# TCAN1146_PWR_MGMT.net
KiCad netlist of a schematic drawn in Altium Designer
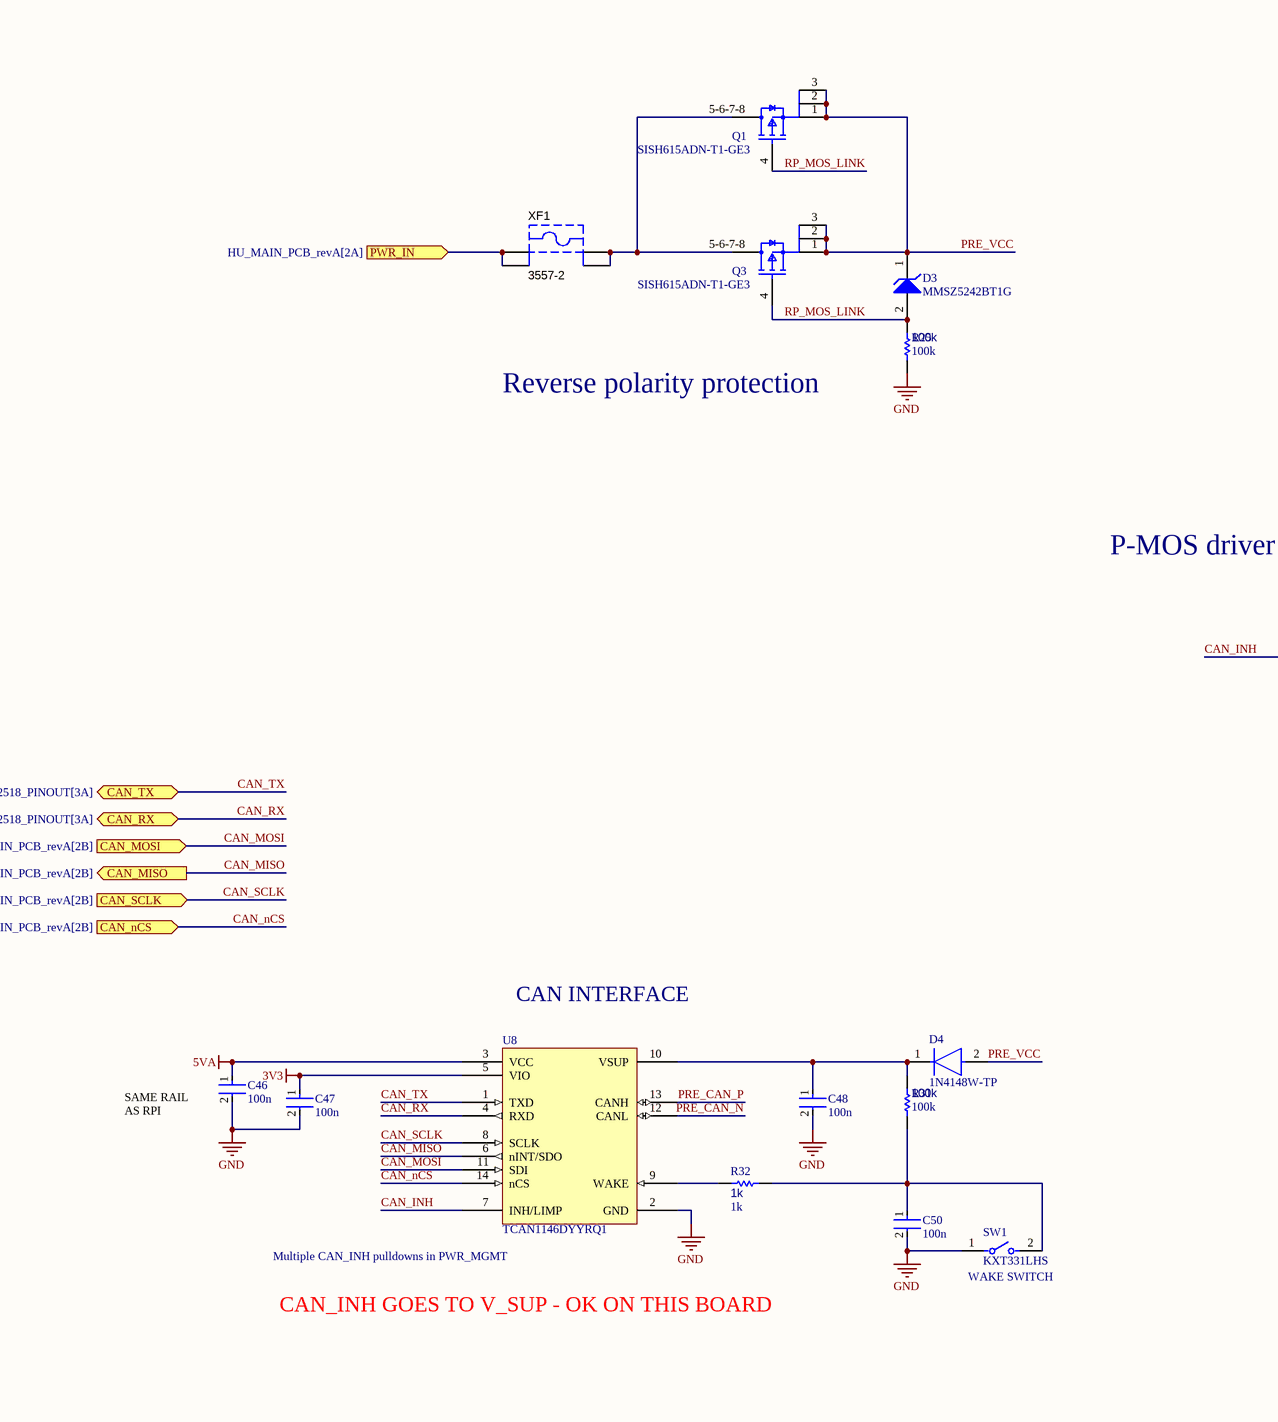
[diagram p0: TCAN1146_PWR_MGMT.SchDoc, left]
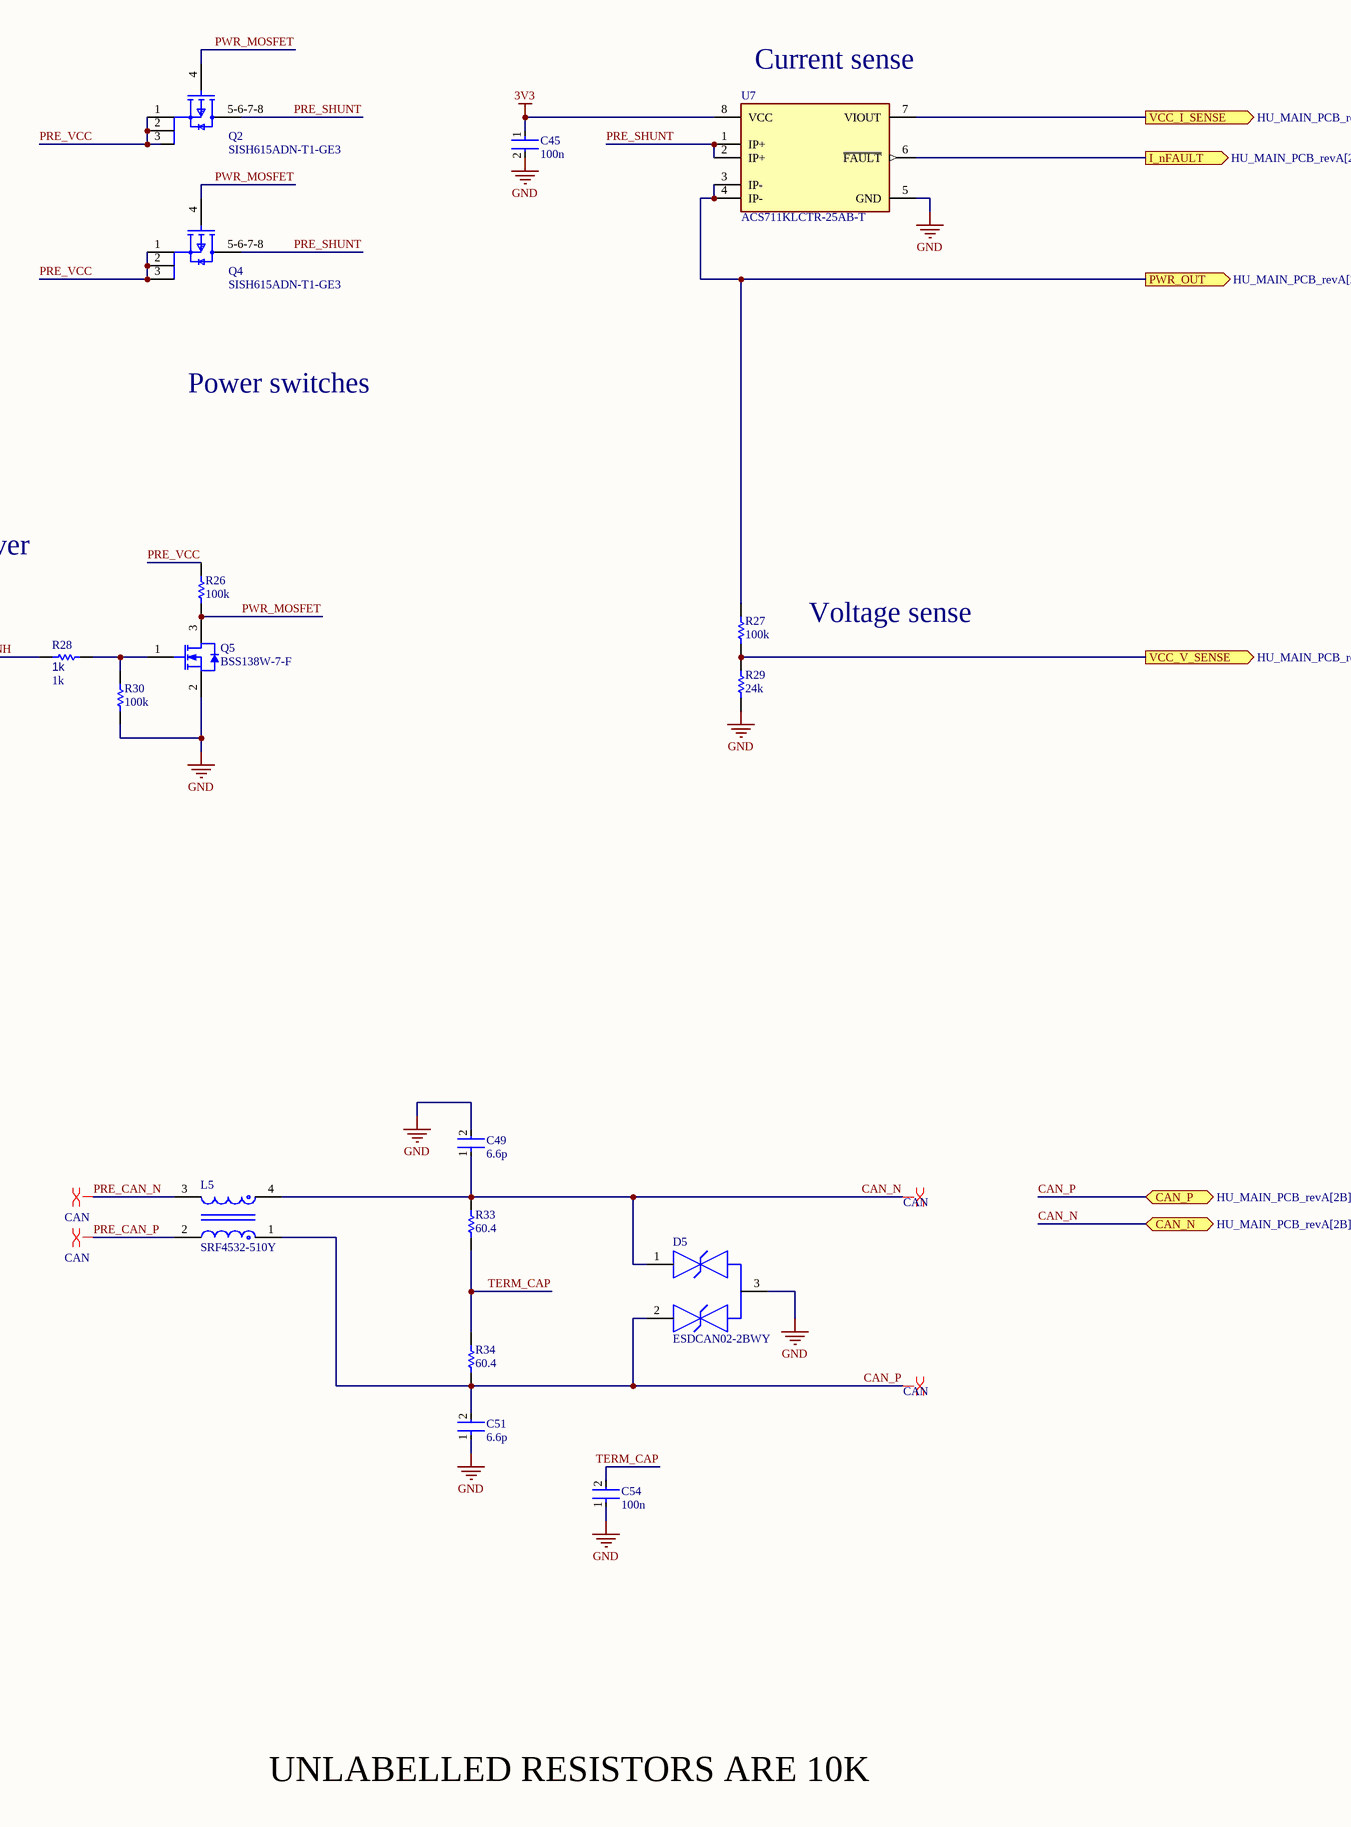
[diagram p1: TCAN1146_PWR_MGMT.SchDoc, right]

(export (version "E")
  (design (tool "Eeschema 10.0.6"))
  (components
    (comp (ref "C45")
      (value "100n")
      (footprint "FP-0402-L_1_0_0_05-W_0_5-IPC_A")
      (description "LARGE PADS, 0402 CAP, CHANGE COMMENT TO MATCH REAL P/N")
      (libsource (lib "Space Concordia") (part "b4654b650e69147ec39a6b967a45e02"))
    )
    (comp (ref "C46")
      (value "100n")
      (footprint "FP-0402-L_1_0_0_05-W_0_5-IPC_A")
      (description "LARGE PADS, 0402 CAP, CHANGE COMMENT TO MATCH REAL P/N")
      (libsource (lib "Space Concordia") (part "b4654b650e69147ec39a6b967a45e02"))
    )
    (comp (ref "C47")
      (value "100n")
      (footprint "FP-0402-L_1_0_0_05-W_0_5-IPC_A")
      (description "LARGE PADS, 0402 CAP, CHANGE COMMENT TO MATCH REAL P/N")
      (libsource (lib "Space Concordia") (part "b4654b650e69147ec39a6b967a45e02"))
    )
    (comp (ref "C48")
      (value "100n")
      (footprint "FP-0402-L_1_0_0_05-W_0_5-IPC_A")
      (description "LARGE PADS, 0402 CAP, CHANGE COMMENT TO MATCH REAL P/N")
      (libsource (lib "Space Concordia") (part "b4654b650e69147ec39a6b967a45e02"))
    )
    (comp (ref "C49")
      (value "6.6p")
      (footprint "FP-0402-L_1_0_0_05-W_0_5-IPC_A")
      (description "LARGE PADS, 0402 CAP, CHANGE COMMENT TO MATCH REAL P/N")
      (libsource (lib "Space Concordia") (part "b4654b650e69147ec39a6b967a45e02"))
    )
    (comp (ref "C50")
      (value "100n")
      (footprint "FP-0402-L_1_0_0_05-W_0_5-IPC_A")
      (description "LARGE PADS, 0402 CAP, CHANGE COMMENT TO MATCH REAL P/N")
      (libsource (lib "Space Concordia") (part "b4654b650e69147ec39a6b967a45e02"))
    )
    (comp (ref "C51")
      (value "6.6p")
      (footprint "FP-0402-L_1_0_0_05-W_0_5-IPC_A")
      (description "LARGE PADS, 0402 CAP, CHANGE COMMENT TO MATCH REAL P/N")
      (libsource (lib "Space Concordia") (part "b4654b650e69147ec39a6b967a45e02"))
    )
    (comp (ref "C54")
      (value "100n")
      (footprint "FP-0402-L_1_0_0_05-W_0_5-IPC_A")
      (description "LARGE PADS, 0402 CAP, CHANGE COMMENT TO MATCH REAL P/N")
      (libsource (lib "Space Concordia") (part "b4654b650e69147ec39a6b967a45e02"))
    )
    (comp (ref "D3")
      (value "MMSZ5242BT1G")
      (footprint "ONSC-SOD-123-2-425-04_V")
      (description "Zener Voltage Regulator, 500 mW, 2-Pin SOD-123, Pb-Free, Tape and Reel")
      (fields (field (name "MANUFACTURER") "On Semiconductor"))
      (libsource (lib "Altium Content Vault") (part "ONSC-K1A2-2"))
    )
    (comp (ref "D4")
      (value "1N4148W-TP")
      (footprint "FP-SOD-123-IPC_A")
      (description "DIODE GEN PURP 100V 150MA SOD123")
      (libsource (lib "Altium Content Vault") (part "d7152d700b627762746794eb795d46e"))
    )
    (comp (ref "D5")
      (value "ESDCAN02-2BWY")
      (footprint "FP-SOT323-3L-MFG")
      (description "TVS DIODE 26.5V 44V SOT323-3")
      (fields
        (field (name "MANUFACTURER") "STMicroelectronics")
        (field (name "OCTOPART") "https://octopart.com/esdcan02-2bwy-stmicroelectronics-58631133")
      )
      (libsource (lib "Altium Content Vault") (part "0b9019fb5e52ed66df21ec1535be59d"))
    )
    (comp (ref "L5")
      (value "SRF4532-510Y")
      (footprint "FP-SRF4532-MFG")
      (description "CMC 51UH 200MA 2LN 2KOHM SMD")
      (fields (field (name "TOLERANCE") "50%"))
      (libsource (lib "Altium Content Vault") (part "aca3f6a10b859f211cca95010157f3b"))
    )
    (comp (ref "Q1")
      (value "SISH615ADN-T1-GE3")
      (footprint "SISH615ADN-T1-GE3-Footprint-1")
      (description "Trans MOSFET P-CH 20V 22.1A 8-Pin PowerPAK 1212 EP T/R")
      (libsource (lib "Space Concordia") (part "CMP-013-00036-4"))
    )
    (comp (ref "Q2")
      (value "SISH615ADN-T1-GE3")
      (footprint "SISH615ADN-T1-GE3-Footprint-1")
      (description "Trans MOSFET P-CH 20V 22.1A 8-Pin PowerPAK 1212 EP T/R")
      (libsource (lib "Space Concordia") (part "CMP-013-00036-4"))
    )
    (comp (ref "Q3")
      (value "SISH615ADN-T1-GE3")
      (footprint "SISH615ADN-T1-GE3-Footprint-1")
      (description "Trans MOSFET P-CH 20V 22.1A 8-Pin PowerPAK 1212 EP T/R")
      (libsource (lib "Space Concordia") (part "CMP-013-00036-4"))
    )
    (comp (ref "Q4")
      (value "SISH615ADN-T1-GE3")
      (footprint "SISH615ADN-T1-GE3-Footprint-1")
      (description "Trans MOSFET P-CH 20V 22.1A 8-Pin PowerPAK 1212 EP T/R")
      (libsource (lib "Space Concordia") (part "CMP-013-00036-4"))
    )
    (comp (ref "Q5")
      (value "BSS138W-7-F")
      (footprint "DIOD-SOT323-3_V")
      (fields (field (name "MANUFACTURER") "DiodesIncorporated"))
      (libsource (lib "Altium Content Vault") (part "NEMOS-GSD-3"))
    )
    (comp (ref "R25")
      (value "100k")
      (footprint "R0603B")
      (description "Resistor")
      (fields (field (name "ALTIUM_VALUE") "100k"))
      (libsource (lib "Space Concordia") (part "Resistor"))
    )
    (comp (ref "R26")
      (value "100k")
      (footprint "R0603B")
      (description "Resistor")
      (libsource (lib "Space Concordia") (part "Resistor"))
    )
    (comp (ref "R27")
      (value "100k")
      (footprint "R0603B")
      (description "Resistor")
      (libsource (lib "Space Concordia") (part "Resistor"))
    )
    (comp (ref "R28")
      (value "1k")
      (footprint "R0603B")
      (description "Resistor")
      (fields (field (name "ALTIUM_VALUE") "1k"))
      (libsource (lib "Space Concordia") (part "Resistor"))
    )
    (comp (ref "R29")
      (value "24k")
      (footprint "R0603B")
      (description "Resistor")
      (libsource (lib "Space Concordia") (part "Resistor"))
    )
    (comp (ref "R30")
      (value "100k")
      (footprint "R0603B")
      (description "Resistor")
      (libsource (lib "Space Concordia") (part "Resistor"))
    )
    (comp (ref "R31")
      (value "100k")
      (footprint "R0603B")
      (description "Resistor")
      (fields (field (name "ALTIUM_VALUE") "100k"))
      (libsource (lib "Space Concordia") (part "Resistor"))
    )
    (comp (ref "R32")
      (value "1k")
      (footprint "R0603B")
      (description "Resistor")
      (fields (field (name "ALTIUM_VALUE") "1k"))
      (libsource (lib "Space Concordia") (part "Resistor"))
    )
    (comp (ref "R33")
      (value "60.4")
      (footprint "R0603B")
      (description "Resistor")
      (libsource (lib "Space Concordia") (part "Resistor"))
    )
    (comp (ref "R34")
      (value "60.4")
      (footprint "R0603B")
      (description "Resistor")
      (libsource (lib "Space Concordia") (part "Resistor"))
    )
    (comp (ref "SW1")
      (value "KXT331LHS")
      (footprint "FP-KXT331LHS-MFG")
      (description "SWITCH TACTILE SPST-NO 0.02A 15V")
      (libsource (lib "Altium Content Vault") (part "bb27bde45df87f1f469753f287ef5ae"))
    )
    (comp (ref "U7")
      (value "ACS711KLCTR-25AB-T")
      (footprint "FP-LC-8-IPC_A")
      (description "SENSOR CURRENT HALL 25A AC/DC")
      (libsource (lib "Altium Content Vault") (part "eeba3158841281b4ae542a6e24976ab"))
    )
    (comp (ref "U8")
      (value "TCAN1146DYYRQ1")
      (footprint "TCAN1146DYYRQ1-Footprint-1")
      (libsource (lib "Space Concordia") (part "CMP-015-00012-2"))
    )
    (comp (ref "XF1")
      (value "3557-2")
      (footprint "KSTN-3557-2")
      (description "FUSE HOLDER, PCB MOUNT, 500VAC, 20A, ROHS")
      (fields (field (name "VOLTAGE") "500V") (field (name "MANUFACTURER") "Keystone-Electronics"))
      (libsource (lib "Altium Content Vault") (part "FUSE_HOLDER-4"))
    )
  )
  (nets
    (net (code "1") (name "/CAN_INH") (class "Default")
      (node (ref "R28") (pin "1") (pinfunction "1_1") (pintype "passive"))
      (node (ref "U8") (pin "7") (pinfunction "INH/LIMP_7") (pintype "passive"))
    )
    (net (code "2") (name "/CAN_MISO") (class "Default")
      (node (ref "U8") (pin "6") (pinfunction "nINT/SDO_6") (pintype "output"))
    )
    (net (code "3") (name "/CAN_MOSI") (class "Default")
      (node (ref "U8") (pin "11") (pinfunction "SDI_11") (pintype "input"))
    )
    (net (code "4") (name "/CAN_N") (class "Default")
      (node (ref "C49") (pin "1") (pinfunction "1_1") (pintype "passive"))
      (node (ref "D5") (pin "1") (pinfunction "1_1") (pintype "passive"))
      (node (ref "L5") (pin "4") (pinfunction "4_4") (pintype "passive"))
      (node (ref "R33") (pin "2") (pinfunction "2_2") (pintype "passive"))
    )
    (net (code "5") (name "/CAN_P") (class "Default")
      (node (ref "C51") (pin "2") (pinfunction "2_2") (pintype "passive"))
      (node (ref "D5") (pin "2") (pinfunction "2_2") (pintype "passive"))
      (node (ref "L5") (pin "1") (pinfunction "1_1") (pintype "passive"))
      (node (ref "R34") (pin "1") (pinfunction "1_1") (pintype "passive"))
    )
    (net (code "6") (name "/CAN_RX") (class "Default")
      (node (ref "U8") (pin "4") (pinfunction "RXD_4") (pintype "output"))
    )
    (net (code "7") (name "/CAN_SCLK") (class "Default")
      (node (ref "U8") (pin "8") (pinfunction "SCLK_8") (pintype "input"))
    )
    (net (code "8") (name "/CAN_TX") (class "Default")
      (node (ref "U8") (pin "1") (pinfunction "TXD_1") (pintype "input"))
    )
    (net (code "9") (name "/CAN_nCS") (class "Default")
      (node (ref "U8") (pin "14") (pinfunction "nCS_14") (pintype "input"))
    )
    (net (code "10") (name "/I_nFAULT") (class "Default")
      (node (ref "U7") (pin "6") (pinfunction "~{FAULT}_6") (pintype "output"))
    )
    (net (code "11") (name "/PRE_CAN_N") (class "Default")
      (node (ref "L5") (pin "3") (pinfunction "3_3") (pintype "passive"))
      (node (ref "U8") (pin "12") (pinfunction "CANL_12") (pintype "bidirectional"))
    )
    (net (code "12") (name "/PRE_CAN_P") (class "Default")
      (node (ref "L5") (pin "2") (pinfunction "2_2") (pintype "passive"))
      (node (ref "U8") (pin "13") (pinfunction "CANH_13") (pintype "bidirectional"))
    )
    (net (code "13") (name "/PRE_SHUNT") (class "Default")
      (node (ref "Q2") (pin "5-6-7-8") (pinfunction "D_5-6-7-8") (pintype "passive"))
      (node (ref "Q4") (pin "5-6-7-8") (pinfunction "D_5-6-7-8") (pintype "passive"))
      (node (ref "U7") (pin "1") (pinfunction "IP+_1") (pintype "passive"))
      (node (ref "U7") (pin "2") (pinfunction "IP+_2") (pintype "passive"))
    )
    (net (code "14") (name "/PRE_VCC") (class "Default")
      (node (ref "D3") (pin "1") (pinfunction "K_1") (pintype "passive"))
      (node (ref "D4") (pin "2") (pinfunction "A_2") (pintype "passive"))
      (node (ref "Q1") (pin "1") (pinfunction "S_1") (pintype "passive"))
      (node (ref "Q1") (pin "2") (pinfunction "S_2") (pintype "passive"))
      (node (ref "Q1") (pin "3") (pinfunction "S_3") (pintype "passive"))
      (node (ref "Q2") (pin "1") (pinfunction "S_1") (pintype "passive"))
      (node (ref "Q2") (pin "2") (pinfunction "S_2") (pintype "passive"))
      (node (ref "Q2") (pin "3") (pinfunction "S_3") (pintype "passive"))
      (node (ref "Q3") (pin "1") (pinfunction "S_1") (pintype "passive"))
      (node (ref "Q3") (pin "2") (pinfunction "S_2") (pintype "passive"))
      (node (ref "Q3") (pin "3") (pinfunction "S_3") (pintype "passive"))
      (node (ref "Q4") (pin "1") (pinfunction "S_1") (pintype "passive"))
      (node (ref "Q4") (pin "2") (pinfunction "S_2") (pintype "passive"))
      (node (ref "Q4") (pin "3") (pinfunction "S_3") (pintype "passive"))
      (node (ref "R26") (pin "2") (pinfunction "2_2") (pintype "passive"))
    )
    (net (code "15") (name "/PWR_IN") (class "Default")
      (node (ref "XF1") (pin "1") (pinfunction "1_1") (pintype "passive"))
      (node (ref "XF1") (pin "2") (pinfunction "2_2") (pintype "passive"))
    )
    (net (code "16") (name "/PWR_MOSFET") (class "Default")
      (node (ref "Q2") (pin "4") (pinfunction "G_4") (pintype "passive"))
      (node (ref "Q4") (pin "4") (pinfunction "G_4") (pintype "passive"))
      (node (ref "Q5") (pin "3") (pinfunction "D_3") (pintype "passive"))
      (node (ref "R26") (pin "1") (pinfunction "1_1") (pintype "passive"))
    )
    (net (code "17") (name "/PWR_OUT") (class "Default")
      (node (ref "R27") (pin "2") (pinfunction "2_2") (pintype "passive"))
      (node (ref "U7") (pin "3") (pinfunction "IP-_3") (pintype "passive"))
      (node (ref "U7") (pin "4") (pinfunction "IP-_4") (pintype "passive"))
    )
    (net (code "18") (name "/RP_MOS_LINK") (class "Default")
      (node (ref "D3") (pin "2") (pinfunction "A_2") (pintype "passive"))
      (node (ref "Q1") (pin "4") (pinfunction "G_4") (pintype "passive"))
      (node (ref "Q3") (pin "4") (pinfunction "G_4") (pintype "passive"))
      (node (ref "R25") (pin "2") (pinfunction "2_2") (pintype "passive"))
    )
    (net (code "19") (name "/TERM_CAP") (class "Default")
      (node (ref "C54") (pin "2") (pinfunction "2_2") (pintype "passive"))
      (node (ref "R33") (pin "1") (pinfunction "1_1") (pintype "passive"))
      (node (ref "R34") (pin "2") (pinfunction "2_2") (pintype "passive"))
    )
    (net (code "20") (name "/VCC_I_SENSE") (class "Default")
      (node (ref "U7") (pin "7") (pinfunction "VIOUT_7") (pintype "passive"))
    )
    (net (code "21") (name "/VCC_V_SENSE") (class "Default")
      (node (ref "R27") (pin "1") (pinfunction "1_1") (pintype "passive"))
      (node (ref "R29") (pin "2") (pinfunction "2_2") (pintype "passive"))
    )
    (net (code "22") (name "3V3") (class "Default")
      (node (ref "C45") (pin "1") (pinfunction "1_1") (pintype "passive"))
      (node (ref "C47") (pin "1") (pinfunction "1_1") (pintype "passive"))
      (node (ref "U7") (pin "8") (pinfunction "VCC_8") (pintype "power_in"))
      (node (ref "U8") (pin "5") (pinfunction "VIO_5") (pintype "power_in"))
    )
    (net (code "23") (name "5VA") (class "Default")
      (node (ref "C46") (pin "1") (pinfunction "1_1") (pintype "passive"))
      (node (ref "U8") (pin "3") (pinfunction "VCC_3") (pintype "power_in"))
    )
    (net (code "24") (name "GND") (class "Default")
      (node (ref "C45") (pin "2") (pinfunction "2_2") (pintype "passive"))
      (node (ref "C46") (pin "2") (pinfunction "2_2") (pintype "passive"))
      (node (ref "C47") (pin "2") (pinfunction "2_2") (pintype "passive"))
      (node (ref "C48") (pin "2") (pinfunction "2_2") (pintype "passive"))
      (node (ref "C49") (pin "2") (pinfunction "2_2") (pintype "passive"))
      (node (ref "C50") (pin "2") (pinfunction "2_2") (pintype "passive"))
      (node (ref "C51") (pin "1") (pinfunction "1_1") (pintype "passive"))
      (node (ref "C54") (pin "1") (pinfunction "1_1") (pintype "passive"))
      (node (ref "D5") (pin "3") (pinfunction "3_3") (pintype "passive"))
      (node (ref "Q5") (pin "2") (pinfunction "S_2") (pintype "passive"))
      (node (ref "R25") (pin "1") (pinfunction "1_1") (pintype "passive"))
      (node (ref "R29") (pin "1") (pinfunction "1_1") (pintype "passive"))
      (node (ref "R30") (pin "1") (pinfunction "1_1") (pintype "passive"))
      (node (ref "SW1") (pin "1") (pinfunction "1_1") (pintype "passive"))
      (node (ref "U7") (pin "5") (pinfunction "GND_5") (pintype "power_in"))
      (node (ref "U8") (pin "2") (pinfunction "GND_2") (pintype "power_in"))
    )
    (net (code "25") (name "Net-(C50-Pad1)") (class "Default")
      (node (ref "C50") (pin "1") (pinfunction "1_1") (pintype "passive"))
      (node (ref "R31") (pin "1") (pinfunction "1_1") (pintype "passive"))
      (node (ref "R32") (pin "2") (pinfunction "2_2") (pintype "passive"))
      (node (ref "SW1") (pin "2") (pinfunction "2_2") (pintype "passive"))
    )
    (net (code "26") (name "Net-(D4-C)") (class "Default")
      (node (ref "C48") (pin "1") (pinfunction "1_1") (pintype "passive"))
      (node (ref "D4") (pin "1") (pinfunction "C_1") (pintype "passive"))
      (node (ref "R31") (pin "2") (pinfunction "2_2") (pintype "passive"))
      (node (ref "U8") (pin "10") (pinfunction "VSUP_10") (pintype "power_in"))
    )
    (net (code "27") (name "Net-(Q1-D)") (class "Default")
      (node (ref "Q1") (pin "5-6-7-8") (pinfunction "D_5-6-7-8") (pintype "passive"))
      (node (ref "Q3") (pin "5-6-7-8") (pinfunction "D_5-6-7-8") (pintype "passive"))
      (node (ref "XF1") (pin "3") (pinfunction "3_3") (pintype "passive"))
      (node (ref "XF1") (pin "4") (pinfunction "4_4") (pintype "passive"))
    )
    (net (code "28") (name "Net-(Q5-G)") (class "Default")
      (node (ref "Q5") (pin "1") (pinfunction "G_1") (pintype "passive"))
      (node (ref "R28") (pin "2") (pinfunction "2_2") (pintype "passive"))
      (node (ref "R30") (pin "2") (pinfunction "2_2") (pintype "passive"))
    )
    (net (code "29") (name "Net-(U8-WAKE)") (class "Default")
      (node (ref "R32") (pin "1") (pinfunction "1_1") (pintype "passive"))
      (node (ref "U8") (pin "9") (pinfunction "WAKE_9") (pintype "input"))
    )
  )
)
